# PC104_52-52.net
KiCad netlist of a schematic drawn in Altium Designer
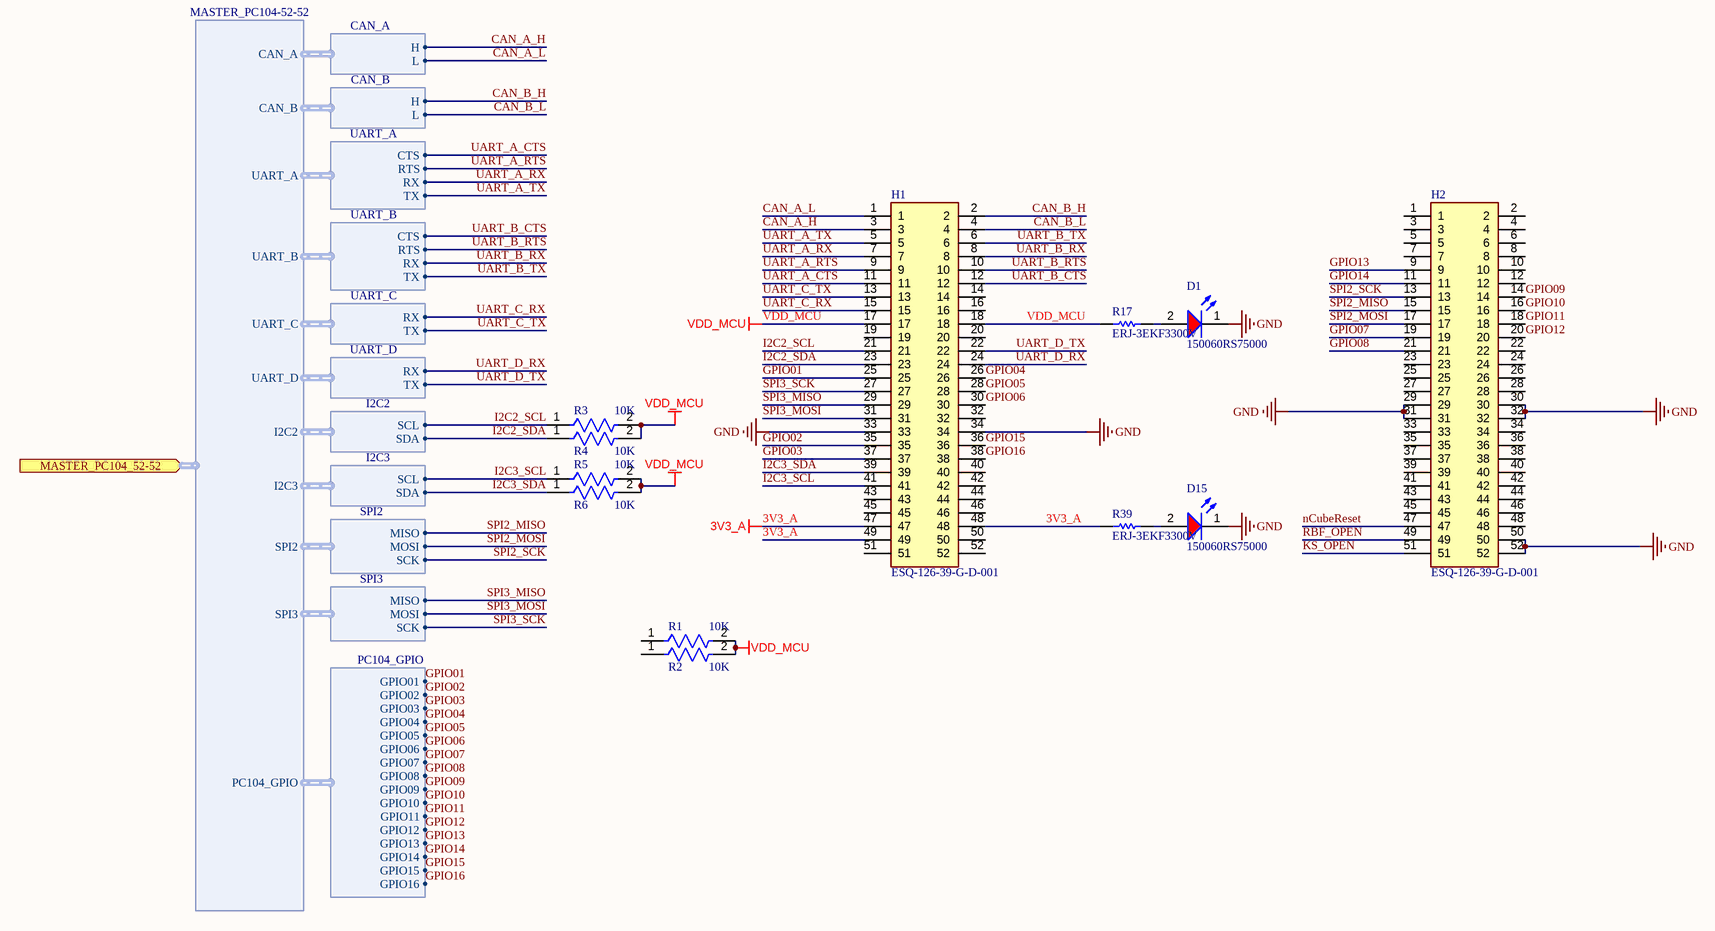
[diagram p0: PC104_52-52.SchDoc]

(export (version "E")
  (design (tool "Eeschema 10.0.6"))
  (components
    (comp (ref "D1")
      (value "150060RS75000")
      (footprint "WL-SMCW_0603_150060xx75000")
      (description "LED Low-Power Uni-Color Red 630nm 2V 2-Pin Chip 0603(1608Metric) T/R")
      (libsource (lib "Altium Content Vault") (part "LED_Red_2A-1K"))
    )
    (comp (ref "D15")
      (value "150060RS75000")
      (footprint "WL-SMCW_0603_150060xx75000")
      (description "LED Low-Power Uni-Color Red 630nm 2V 2-Pin Chip 0603(1608Metric) T/R")
      (libsource (lib "Altium Content Vault") (part "LED_Red_2A-1K"))
    )
    (comp (ref "H1")
      (value "ESQ-126-39-G-D-001")
      (footprint "RHDR52W64P254_2X26_6654X495X1135P")
      (description "PC / 104 Connectors Elevated Socket Strip")
      (fields (field (name "MOUSER PART NUMBER") "200-ESQ12639GD001"))
      (libsource (lib "Hitesh Bhoyar") (part "ESQ-126-39-G-D-001"))
    )
    (comp (ref "H2")
      (value "ESQ-126-39-G-D-001")
      (footprint "RHDR52W64P254_2X26_6654X495X1135P")
      (description "PC / 104 Connectors Elevated Socket Strip")
      (fields (field (name "MOUSER PART NUMBER") "200-ESQ12639GD001"))
      (libsource (lib "Hitesh Bhoyar") (part "ESQ-126-39-G-D-001"))
    )
    (comp (ref "R1")
      (value "10K")
      (footprint "FP-RK73B1J-MFG")
      (description "RES 10K OHM 5% 1/10W 0603")
      (fields (field (name "TOLERANCE") "5%"))
      (libsource (lib "Altium Content Vault") (part "1029c3af85768c4190bb7ad29bc67b5"))
    )
    (comp (ref "R2")
      (value "10K")
      (footprint "FP-RK73B1J-MFG")
      (description "RES 10K OHM 5% 1/10W 0603")
      (fields (field (name "TOLERANCE") "5%"))
      (libsource (lib "Altium Content Vault") (part "1029c3af85768c4190bb7ad29bc67b5"))
    )
    (comp (ref "R3")
      (value "10K")
      (footprint "FP-RK73B1J-MFG")
      (description "RES 10K OHM 5% 1/10W 0603")
      (fields (field (name "TOLERANCE") "5%"))
      (libsource (lib "Altium Content Vault") (part "1029c3af85768c4190bb7ad29bc67b5"))
    )
    (comp (ref "R4")
      (value "10K")
      (footprint "FP-RK73B1J-MFG")
      (description "RES 10K OHM 5% 1/10W 0603")
      (fields (field (name "TOLERANCE") "5%"))
      (libsource (lib "Altium Content Vault") (part "1029c3af85768c4190bb7ad29bc67b5"))
    )
    (comp (ref "R5")
      (value "10K")
      (footprint "FP-RK73B1J-MFG")
      (description "RES 10K OHM 5% 1/10W 0603")
      (fields (field (name "TOLERANCE") "5%"))
      (libsource (lib "Altium Content Vault") (part "1029c3af85768c4190bb7ad29bc67b5"))
    )
    (comp (ref "R6")
      (value "10K")
      (footprint "FP-RK73B1J-MFG")
      (description "RES 10K OHM 5% 1/10W 0603")
      (fields (field (name "TOLERANCE") "5%"))
      (libsource (lib "Altium Content Vault") (part "1029c3af85768c4190bb7ad29bc67b5"))
    )
    (comp (ref "R17")
      (value "ERJ-3EKF3300V")
      (footprint "RESC1608X55X30LL15T15")
      (description "Chip Resistor, 330 Ohm, +/- 1%, 0.1 W, -55 to 155 degC, 0603 (1608 Metric), RoHS, Tape and Reel")
      (libsource (lib "Altium Content Vault") (part "RES-2"))
    )
    (comp (ref "R39")
      (value "ERJ-3EKF3300V")
      (footprint "RESC1608X55X30LL15T15")
      (description "Chip Resistor, 330 Ohm, +/- 1%, 0.1 W, -55 to 155 degC, 0603 (1608 Metric), RoHS, Tape and Reel")
      (libsource (lib "Altium Content Vault") (part "RES-2"))
    )
  )
  (nets
    (net (code "13") (name "/CAN_A_H") (class "Default")
      (node (ref "H1") (pin "3") (pinfunction "3_3") (pintype "passive"))
    )
    (net (code "14") (name "/CAN_A_L") (class "Default")
      (node (ref "H1") (pin "1") (pinfunction "1_1") (pintype "passive"))
    )
    (net (code "15") (name "/CAN_B_H") (class "Default")
      (node (ref "H1") (pin "2") (pinfunction "2_2") (pintype "passive"))
    )
    (net (code "16") (name "/CAN_B_L") (class "Default")
      (node (ref "H1") (pin "4") (pinfunction "4_4") (pintype "passive"))
    )
    (net (code "17") (name "/GPIO01") (class "Default")
      (node (ref "H1") (pin "25") (pinfunction "25_25") (pintype "passive"))
    )
    (net (code "18") (name "/GPIO02") (class "Default")
      (node (ref "H1") (pin "35") (pinfunction "35_35") (pintype "passive"))
    )
    (net (code "19") (name "/GPIO03") (class "Default")
      (node (ref "H1") (pin "37") (pinfunction "37_37") (pintype "passive"))
    )
    (net (code "20") (name "/GPIO04") (class "Default")
      (node (ref "H1") (pin "26") (pinfunction "26_26") (pintype "passive"))
    )
    (net (code "21") (name "/GPIO05") (class "Default")
      (node (ref "H1") (pin "28") (pinfunction "28_28") (pintype "passive"))
    )
    (net (code "22") (name "/GPIO06") (class "Default")
      (node (ref "H1") (pin "30") (pinfunction "30_30") (pintype "passive"))
    )
    (net (code "23") (name "/GPIO07") (class "Default")
      (node (ref "H2") (pin "19") (pinfunction "19_19") (pintype "passive"))
    )
    (net (code "24") (name "/GPIO08") (class "Default")
      (node (ref "H2") (pin "21") (pinfunction "21_21") (pintype "passive"))
    )
    (net (code "25") (name "/GPIO09") (class "Default")
      (node (ref "H2") (pin "14") (pinfunction "14_14") (pintype "passive"))
    )
    (net (code "26") (name "/GPIO10") (class "Default")
      (node (ref "H2") (pin "16") (pinfunction "16_16") (pintype "passive"))
    )
    (net (code "27") (name "/GPIO11") (class "Default")
      (node (ref "H2") (pin "18") (pinfunction "18_18") (pintype "passive"))
    )
    (net (code "28") (name "/GPIO12") (class "Default")
      (node (ref "H2") (pin "20") (pinfunction "20_20") (pintype "passive"))
    )
    (net (code "29") (name "/GPIO13") (class "Default")
      (node (ref "H2") (pin "9") (pinfunction "9_9") (pintype "passive"))
    )
    (net (code "30") (name "/GPIO14") (class "Default")
      (node (ref "H2") (pin "11") (pinfunction "11_11") (pintype "passive"))
    )
    (net (code "31") (name "/GPIO15") (class "Default")
      (node (ref "H1") (pin "36") (pinfunction "36_36") (pintype "passive"))
    )
    (net (code "32") (name "/GPIO16") (class "Default")
      (node (ref "H1") (pin "38") (pinfunction "38_38") (pintype "passive"))
    )
    (net (code "33") (name "/I2C2_SCL") (class "Default")
      (node (ref "H1") (pin "21") (pinfunction "21_21") (pintype "passive"))
      (node (ref "R3") (pin "1") (pinfunction "1_1") (pintype "passive"))
    )
    (net (code "34") (name "/I2C2_SDA") (class "Default")
      (node (ref "H1") (pin "23") (pinfunction "23_23") (pintype "passive"))
      (node (ref "R4") (pin "1") (pinfunction "1_1") (pintype "passive"))
    )
    (net (code "35") (name "/I2C3_SCL") (class "Default")
      (node (ref "H1") (pin "41") (pinfunction "41_41") (pintype "passive"))
      (node (ref "R5") (pin "1") (pinfunction "1_1") (pintype "passive"))
    )
    (net (code "36") (name "/I2C3_SDA") (class "Default")
      (node (ref "H1") (pin "39") (pinfunction "39_39") (pintype "passive"))
      (node (ref "R6") (pin "1") (pinfunction "1_1") (pintype "passive"))
    )
    (net (code "37") (name "/KS_OPEN") (class "Default")
      (node (ref "H2") (pin "51") (pinfunction "51_51") (pintype "passive"))
    )
    (net (code "39") (name "/RBF_OPEN") (class "Default")
      (node (ref "H2") (pin "49") (pinfunction "49_49") (pintype "passive"))
    )
    (net (code "40") (name "/SPI2_MISO") (class "Default")
      (node (ref "H2") (pin "15") (pinfunction "15_15") (pintype "passive"))
    )
    (net (code "41") (name "/SPI2_MOSI") (class "Default")
      (node (ref "H2") (pin "17") (pinfunction "17_17") (pintype "passive"))
    )
    (net (code "42") (name "/SPI2_SCK") (class "Default")
      (node (ref "H2") (pin "13") (pinfunction "13_13") (pintype "passive"))
    )
    (net (code "43") (name "/SPI3_MISO") (class "Default")
      (node (ref "H1") (pin "29") (pinfunction "29_29") (pintype "passive"))
    )
    (net (code "44") (name "/SPI3_MOSI") (class "Default")
      (node (ref "H1") (pin "31") (pinfunction "31_31") (pintype "passive"))
    )
    (net (code "45") (name "/SPI3_SCK") (class "Default")
      (node (ref "H1") (pin "27") (pinfunction "27_27") (pintype "passive"))
    )
    (net (code "46") (name "/UART_A_CTS") (class "Default")
      (node (ref "H1") (pin "11") (pinfunction "11_11") (pintype "passive"))
    )
    (net (code "47") (name "/UART_A_RTS") (class "Default")
      (node (ref "H1") (pin "9") (pinfunction "9_9") (pintype "passive"))
    )
    (net (code "48") (name "/UART_A_RX") (class "Default")
      (node (ref "H1") (pin "7") (pinfunction "7_7") (pintype "passive"))
    )
    (net (code "49") (name "/UART_A_TX") (class "Default")
      (node (ref "H1") (pin "5") (pinfunction "5_5") (pintype "passive"))
    )
    (net (code "50") (name "/UART_B_CTS") (class "Default")
      (node (ref "H1") (pin "12") (pinfunction "12_12") (pintype "passive"))
    )
    (net (code "51") (name "/UART_B_RTS") (class "Default")
      (node (ref "H1") (pin "10") (pinfunction "10_10") (pintype "passive"))
    )
    (net (code "52") (name "/UART_B_RX") (class "Default")
      (node (ref "H1") (pin "8") (pinfunction "8_8") (pintype "passive"))
    )
    (net (code "53") (name "/UART_B_TX") (class "Default")
      (node (ref "H1") (pin "6") (pinfunction "6_6") (pintype "passive"))
    )
    (net (code "54") (name "/UART_C_RX") (class "Default")
      (node (ref "H1") (pin "15") (pinfunction "15_15") (pintype "passive"))
    )
    (net (code "55") (name "/UART_C_TX") (class "Default")
      (node (ref "H1") (pin "13") (pinfunction "13_13") (pintype "passive"))
    )
    (net (code "56") (name "/UART_D_RX") (class "Default")
      (node (ref "H1") (pin "24") (pinfunction "24_24") (pintype "passive"))
    )
    (net (code "57") (name "/UART_D_TX") (class "Default")
      (node (ref "H1") (pin "22") (pinfunction "22_22") (pintype "passive"))
    )
    (net (code "58") (name "/nCubeReset") (class "Default")
      (node (ref "H2") (pin "47") (pinfunction "47_47") (pintype "passive"))
    )
    (net (code "70") (name "3V3_A") (class "Default")
      (node (ref "H1") (pin "47") (pinfunction "47_47") (pintype "passive"))
      (node (ref "H1") (pin "48") (pinfunction "48_48") (pintype "passive"))
      (node (ref "H1") (pin "49") (pinfunction "49_49") (pintype "passive"))
      (node (ref "R39") (pin "1") (pinfunction "1_1") (pintype "passive"))
    )
    (net (code "71") (name "GND") (class "Default")
      (node (ref "D1") (pin "1") (pinfunction "K_1") (pintype "passive"))
      (node (ref "D15") (pin "1") (pinfunction "K_1") (pintype "passive"))
      (node (ref "H1") (pin "33") (pinfunction "33_33") (pintype "passive"))
      (node (ref "H1") (pin "34") (pinfunction "34_34") (pintype "passive"))
      (node (ref "H2") (pin "29") (pinfunction "29_29") (pintype "passive"))
      (node (ref "H2") (pin "30") (pinfunction "30_30") (pintype "passive"))
      (node (ref "H2") (pin "31") (pinfunction "31_31") (pintype "passive"))
      (node (ref "H2") (pin "32") (pinfunction "32_32") (pintype "passive"))
      (node (ref "H2") (pin "50") (pinfunction "50_50") (pintype "passive"))
      (node (ref "H2") (pin "52") (pinfunction "52_52") (pintype "passive"))
    )
    (net (code "72") (name "Net-(D1-A)") (class "Default")
      (node (ref "D1") (pin "2") (pinfunction "A_2") (pintype "passive"))
      (node (ref "R17") (pin "2") (pinfunction "2_2") (pintype "passive"))
    )
    (net (code "73") (name "Net-(D15-A)") (class "Default")
      (node (ref "D15") (pin "2") (pinfunction "A_2") (pintype "passive"))
      (node (ref "R39") (pin "2") (pinfunction "2_2") (pintype "passive"))
    )
    (net (code "74") (name "VDD_MCU") (class "Default")
      (node (ref "H1") (pin "17") (pinfunction "17_17") (pintype "passive"))
      (node (ref "H1") (pin "18") (pinfunction "18_18") (pintype "passive"))
      (node (ref "R1") (pin "2") (pinfunction "2_2") (pintype "passive"))
      (node (ref "R17") (pin "1") (pinfunction "1_1") (pintype "passive"))
      (node (ref "R2") (pin "2") (pinfunction "2_2") (pintype "passive"))
      (node (ref "R3") (pin "2") (pinfunction "2_2") (pintype "passive"))
      (node (ref "R4") (pin "2") (pinfunction "2_2") (pintype "passive"))
      (node (ref "R5") (pin "2") (pinfunction "2_2") (pintype "passive"))
      (node (ref "R6") (pin "2") (pinfunction "2_2") (pintype "passive"))
    )
    (net (code "75") (name "unconnected-(H1-Pad14)") (class "Default")
      (node (ref "H1") (pin "14") (pinfunction "14_14") (pintype "passive"))
    )
    (net (code "76") (name "unconnected-(H1-Pad16)") (class "Default")
      (node (ref "H1") (pin "16") (pinfunction "16_16") (pintype "passive"))
    )
    (net (code "77") (name "unconnected-(H1-Pad19)") (class "Default")
      (node (ref "H1") (pin "19") (pinfunction "19_19") (pintype "passive"))
    )
    (net (code "78") (name "unconnected-(H1-Pad20)") (class "Default")
      (node (ref "H1") (pin "20") (pinfunction "20_20") (pintype "passive"))
    )
    (net (code "79") (name "unconnected-(H1-Pad32)") (class "Default")
      (node (ref "H1") (pin "32") (pinfunction "32_32") (pintype "passive"))
    )
    (net (code "80") (name "unconnected-(H1-Pad40)") (class "Default")
      (node (ref "H1") (pin "40") (pinfunction "40_40") (pintype "passive"))
    )
    (net (code "81") (name "unconnected-(H1-Pad42)") (class "Default")
      (node (ref "H1") (pin "42") (pinfunction "42_42") (pintype "passive"))
    )
    (net (code "82") (name "unconnected-(H1-Pad43)") (class "Default")
      (node (ref "H1") (pin "43") (pinfunction "43_43") (pintype "passive"))
    )
    (net (code "83") (name "unconnected-(H1-Pad44)") (class "Default")
      (node (ref "H1") (pin "44") (pinfunction "44_44") (pintype "passive"))
    )
    (net (code "84") (name "unconnected-(H1-Pad45)") (class "Default")
      (node (ref "H1") (pin "45") (pinfunction "45_45") (pintype "passive"))
    )
    (net (code "85") (name "unconnected-(H1-Pad46)") (class "Default")
      (node (ref "H1") (pin "46") (pinfunction "46_46") (pintype "passive"))
    )
    (net (code "86") (name "unconnected-(H1-Pad50)") (class "Default")
      (node (ref "H1") (pin "50") (pinfunction "50_50") (pintype "passive"))
    )
    (net (code "87") (name "unconnected-(H1-Pad51)") (class "Default")
      (node (ref "H1") (pin "51") (pinfunction "51_51") (pintype "passive"))
    )
    (net (code "88") (name "unconnected-(H1-Pad52)") (class "Default")
      (node (ref "H1") (pin "52") (pinfunction "52_52") (pintype "passive"))
    )
    (net (code "89") (name "unconnected-(H2-Pad1)") (class "Default")
      (node (ref "H2") (pin "1") (pinfunction "1_1") (pintype "passive"))
    )
    (net (code "90") (name "unconnected-(H2-Pad2)") (class "Default")
      (node (ref "H2") (pin "2") (pinfunction "2_2") (pintype "passive"))
    )
    (net (code "91") (name "unconnected-(H2-Pad3)") (class "Default")
      (node (ref "H2") (pin "3") (pinfunction "3_3") (pintype "passive"))
    )
    (net (code "92") (name "unconnected-(H2-Pad4)") (class "Default")
      (node (ref "H2") (pin "4") (pinfunction "4_4") (pintype "passive"))
    )
    (net (code "93") (name "unconnected-(H2-Pad5)") (class "Default")
      (node (ref "H2") (pin "5") (pinfunction "5_5") (pintype "passive"))
    )
    (net (code "94") (name "unconnected-(H2-Pad6)") (class "Default")
      (node (ref "H2") (pin "6") (pinfunction "6_6") (pintype "passive"))
    )
    (net (code "95") (name "unconnected-(H2-Pad7)") (class "Default")
      (node (ref "H2") (pin "7") (pinfunction "7_7") (pintype "passive"))
    )
    (net (code "96") (name "unconnected-(H2-Pad8)") (class "Default")
      (node (ref "H2") (pin "8") (pinfunction "8_8") (pintype "passive"))
    )
    (net (code "97") (name "unconnected-(H2-Pad10)") (class "Default")
      (node (ref "H2") (pin "10") (pinfunction "10_10") (pintype "passive"))
    )
    (net (code "98") (name "unconnected-(H2-Pad12)") (class "Default")
      (node (ref "H2") (pin "12") (pinfunction "12_12") (pintype "passive"))
    )
    (net (code "99") (name "unconnected-(H2-Pad22)") (class "Default")
      (node (ref "H2") (pin "22") (pinfunction "22_22") (pintype "passive"))
    )
    (net (code "100") (name "unconnected-(H2-Pad23)") (class "Default")
      (node (ref "H2") (pin "23") (pinfunction "23_23") (pintype "passive"))
    )
    (net (code "101") (name "unconnected-(H2-Pad24)") (class "Default")
      (node (ref "H2") (pin "24") (pinfunction "24_24") (pintype "passive"))
    )
    (net (code "102") (name "unconnected-(H2-Pad25)") (class "Default")
      (node (ref "H2") (pin "25") (pinfunction "25_25") (pintype "passive"))
    )
    (net (code "103") (name "unconnected-(H2-Pad26)") (class "Default")
      (node (ref "H2") (pin "26") (pinfunction "26_26") (pintype "passive"))
    )
    (net (code "104") (name "unconnected-(H2-Pad27)") (class "Default")
      (node (ref "H2") (pin "27") (pinfunction "27_27") (pintype "passive"))
    )
    (net (code "105") (name "unconnected-(H2-Pad28)") (class "Default")
      (node (ref "H2") (pin "28") (pinfunction "28_28") (pintype "passive"))
    )
    (net (code "106") (name "unconnected-(H2-Pad33)") (class "Default")
      (node (ref "H2") (pin "33") (pinfunction "33_33") (pintype "passive"))
    )
    (net (code "107") (name "unconnected-(H2-Pad34)") (class "Default")
      (node (ref "H2") (pin "34") (pinfunction "34_34") (pintype "passive"))
    )
    (net (code "108") (name "unconnected-(H2-Pad35)") (class "Default")
      (node (ref "H2") (pin "35") (pinfunction "35_35") (pintype "passive"))
    )
    (net (code "109") (name "unconnected-(H2-Pad36)") (class "Default")
      (node (ref "H2") (pin "36") (pinfunction "36_36") (pintype "passive"))
    )
    (net (code "110") (name "unconnected-(H2-Pad37)") (class "Default")
      (node (ref "H2") (pin "37") (pinfunction "37_37") (pintype "passive"))
    )
    (net (code "111") (name "unconnected-(H2-Pad38)") (class "Default")
      (node (ref "H2") (pin "38") (pinfunction "38_38") (pintype "passive"))
    )
    (net (code "112") (name "unconnected-(H2-Pad39)") (class "Default")
      (node (ref "H2") (pin "39") (pinfunction "39_39") (pintype "passive"))
    )
    (net (code "113") (name "unconnected-(H2-Pad40)") (class "Default")
      (node (ref "H2") (pin "40") (pinfunction "40_40") (pintype "passive"))
    )
    (net (code "114") (name "unconnected-(H2-Pad41)") (class "Default")
      (node (ref "H2") (pin "41") (pinfunction "41_41") (pintype "passive"))
    )
    (net (code "115") (name "unconnected-(H2-Pad42)") (class "Default")
      (node (ref "H2") (pin "42") (pinfunction "42_42") (pintype "passive"))
    )
    (net (code "116") (name "unconnected-(H2-Pad43)") (class "Default")
      (node (ref "H2") (pin "43") (pinfunction "43_43") (pintype "passive"))
    )
    (net (code "117") (name "unconnected-(H2-Pad44)") (class "Default")
      (node (ref "H2") (pin "44") (pinfunction "44_44") (pintype "passive"))
    )
    (net (code "118") (name "unconnected-(H2-Pad45)") (class "Default")
      (node (ref "H2") (pin "45") (pinfunction "45_45") (pintype "passive"))
    )
    (net (code "119") (name "unconnected-(H2-Pad46)") (class "Default")
      (node (ref "H2") (pin "46") (pinfunction "46_46") (pintype "passive"))
    )
    (net (code "120") (name "unconnected-(H2-Pad48)") (class "Default")
      (node (ref "H2") (pin "48") (pinfunction "48_48") (pintype "passive"))
    )
    (net (code "121") (name "unconnected-(R1-Pad1)") (class "Default")
      (node (ref "R1") (pin "1") (pinfunction "1_1") (pintype "passive"))
    )
    (net (code "122") (name "unconnected-(R2-Pad1)") (class "Default")
      (node (ref "R2") (pin "1") (pinfunction "1_1") (pintype "passive"))
    )
  )
)
